# Schematic.net
KiCad netlist of a schematic drawn in EAGLE
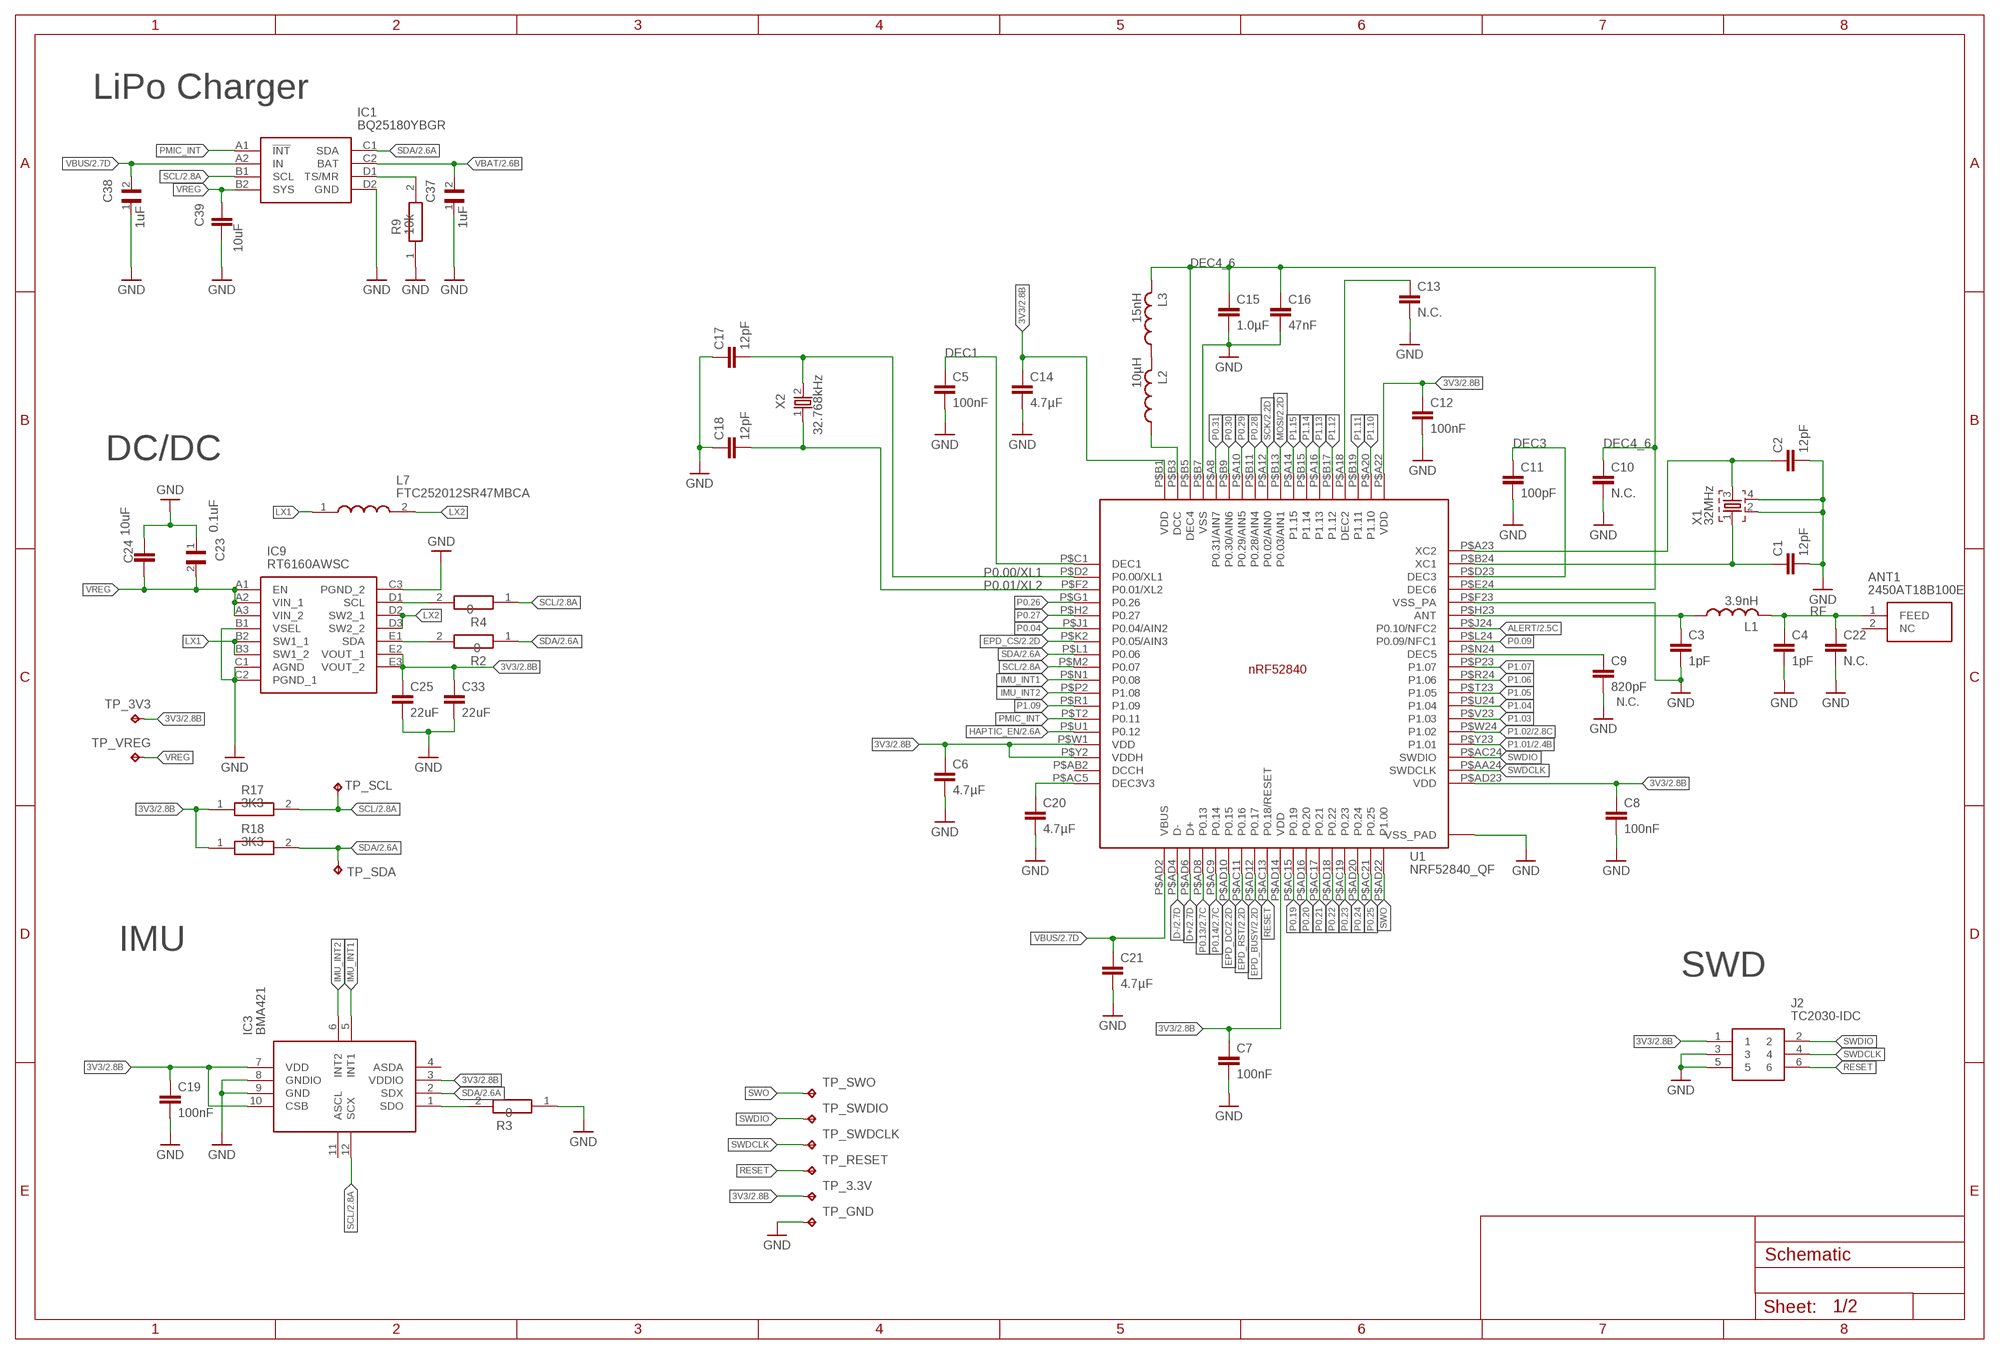
[diagram p0: schematic, sheet 1]
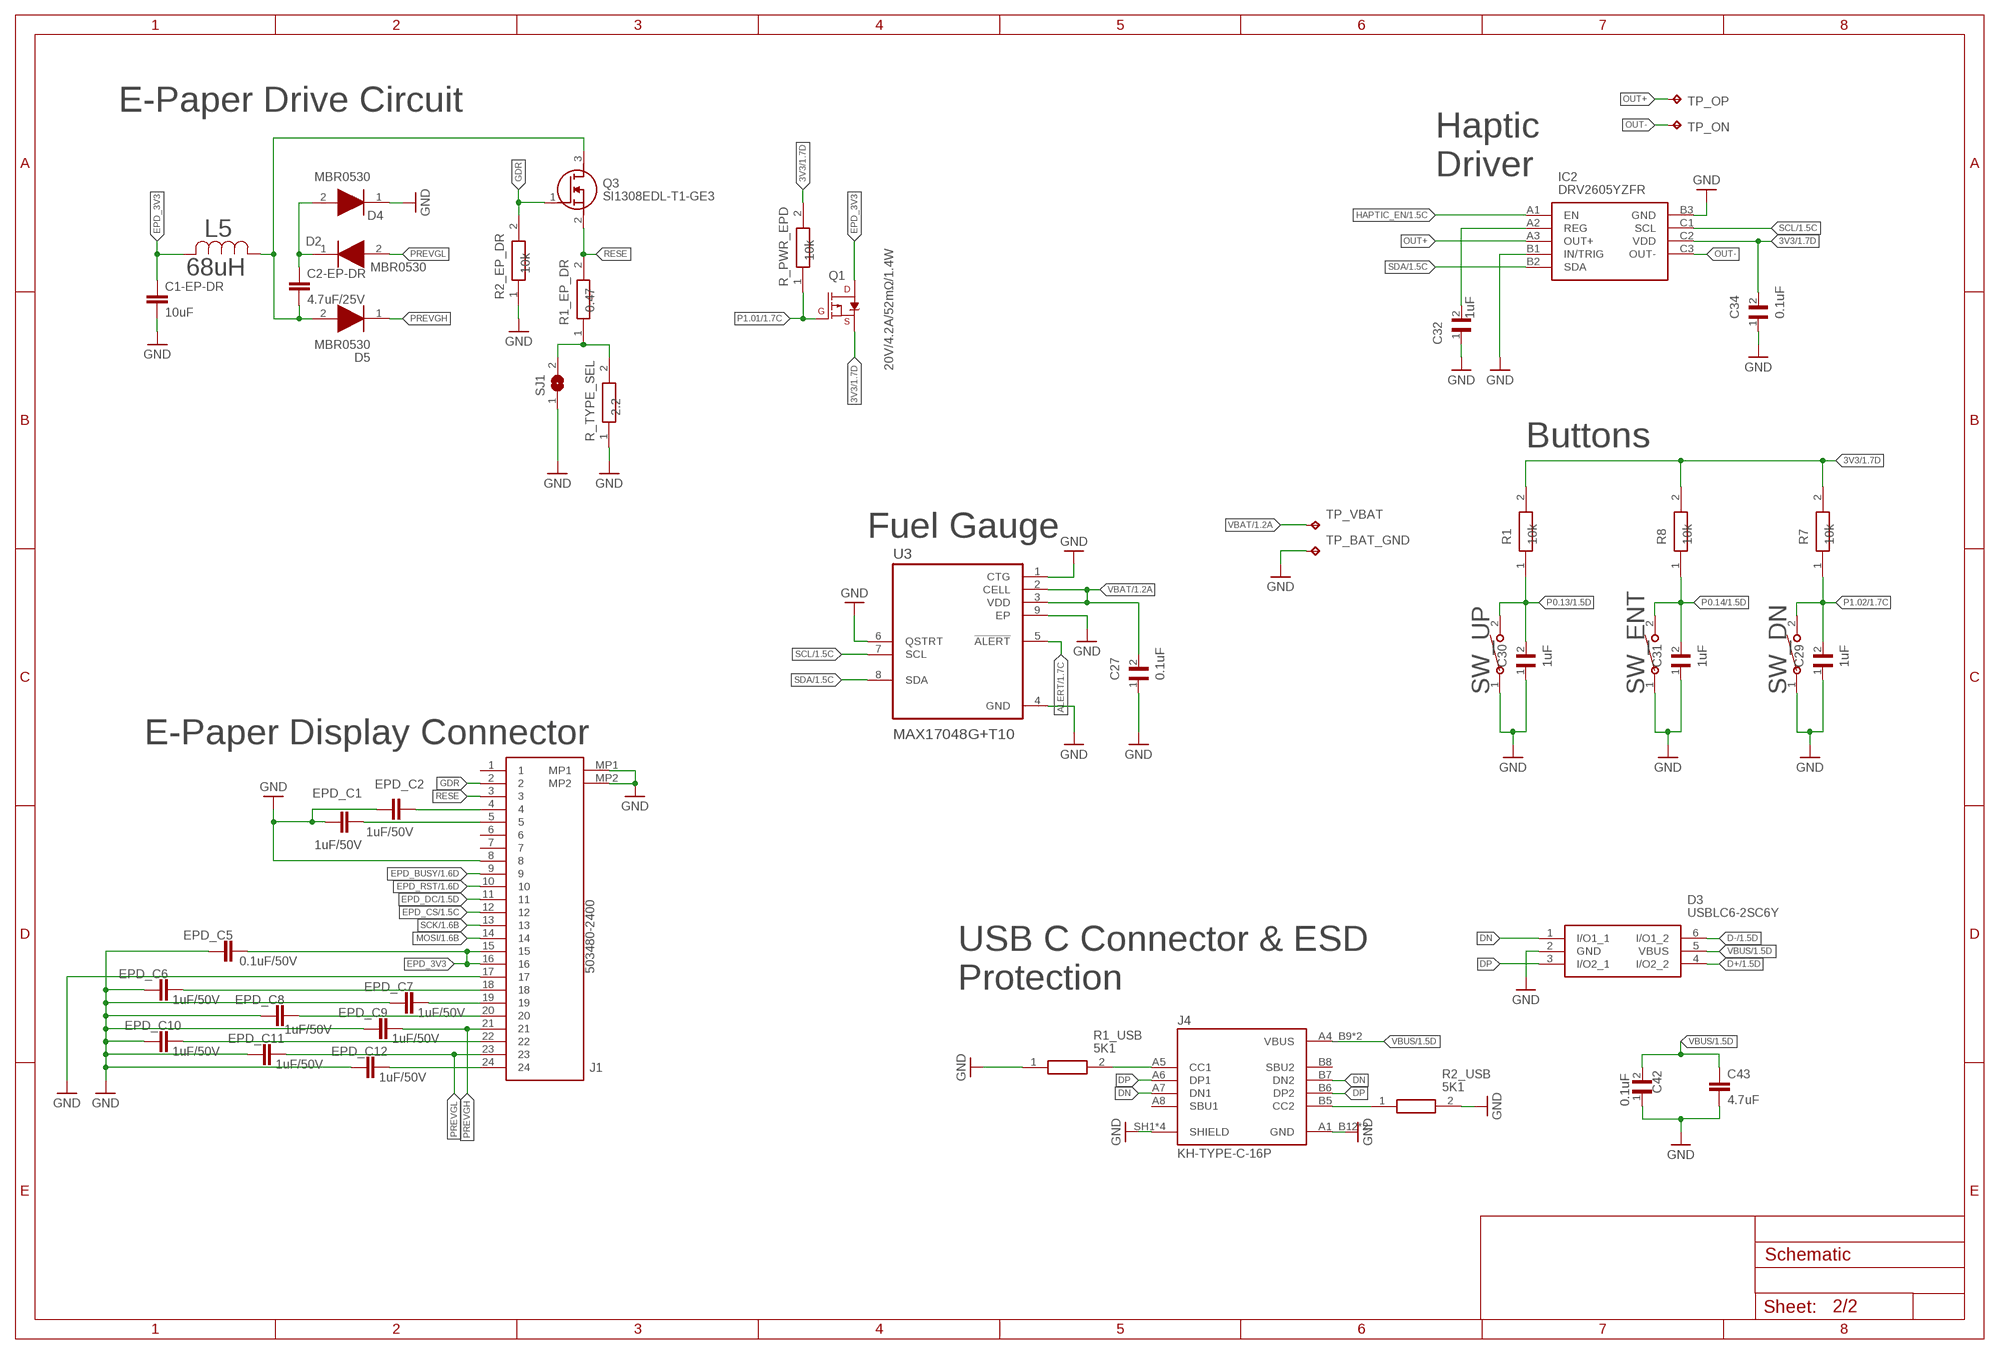
[diagram p1: schematic, sheet 2]

(export (version "E")
  (design (tool "Eeschema 10.0.6"))
  (components
    (comp (ref "ANT1")
      (value "2450AT18B100E")
      (footprint "eagle-import:2450AT18B100E_ANTC3216X140N")
      (fields (field (name "MOUSER_PART_NUMBER") "609-2450AT18B100E"))
      (libsource (lib "eagle-import") (part "2450AT18B100E_2450AT18B100E"))
    )
    (comp (ref "C1")
      (value "12pF")
      (footprint "eagle-import:NORDIC_NRF_3_RESC0201_L")
      (libsource (lib "eagle-import") (part "NORDIC_NRF_3_CAPACITOR_0201_L"))
    )
    (comp (ref "C2")
      (value "12pF")
      (footprint "eagle-import:NORDIC_NRF_3_RESC0201_L")
      (libsource (lib "eagle-import") (part "NORDIC_NRF_3_CAPACITOR_0201_L"))
    )
    (comp (ref "C3")
      (value "1pF")
      (footprint "eagle-import:NORDIC_NRF_3_RESC0201_L")
      (libsource (lib "eagle-import") (part "NORDIC_NRF_3_CAPACITOR_0201_L"))
    )
    (comp (ref "C4")
      (value "1pF")
      (footprint "eagle-import:NORDIC_NRF_3_RESC0201_L")
      (libsource (lib "eagle-import") (part "NORDIC_NRF_3_CAPACITOR_0201_L"))
    )
    (comp (ref "C5")
      (value "100nF")
      (footprint "eagle-import:NORDIC_NRF_3_RESC0201_L")
      (libsource (lib "eagle-import") (part "NORDIC_NRF_3_CAPACITOR_0201_L"))
    )
    (comp (ref "C6")
      (value "4.7µF")
      (footprint "eagle-import:NORDIC_NRF_3_RESC0201_L")
      (libsource (lib "eagle-import") (part "NORDIC_NRF_3_CAPACITOR_0201_L"))
    )
    (comp (ref "C7")
      (value "100nF")
      (footprint "eagle-import:NORDIC_NRF_3_RESC0201_L")
      (libsource (lib "eagle-import") (part "NORDIC_NRF_3_CAPACITOR_0201_L"))
    )
    (comp (ref "C8")
      (value "100nF")
      (footprint "eagle-import:NORDIC_NRF_3_RESC0201_L")
      (libsource (lib "eagle-import") (part "NORDIC_NRF_3_CAPACITOR_0201_L"))
    )
    (comp (ref "C9")
      (value "820pF")
      (footprint "eagle-import:NORDIC_NRF_3_RESC0201_L")
      (libsource (lib "eagle-import") (part "NORDIC_NRF_3_CAPACITOR_0201_L"))
    )
    (comp (ref "C10")
      (value "N.C.")
      (footprint "eagle-import:NORDIC_NRF_3_RESC0201_L")
      (libsource (lib "eagle-import") (part "NORDIC_NRF_3_CAPACITOR_0201_L"))
    )
    (comp (ref "C11")
      (value "100pF")
      (footprint "eagle-import:NORDIC_NRF_3_RESC0201_L")
      (libsource (lib "eagle-import") (part "NORDIC_NRF_3_CAPACITOR_0201_L"))
    )
    (comp (ref "C12")
      (value "100nF")
      (footprint "eagle-import:NORDIC_NRF_3_RESC0201_L")
      (libsource (lib "eagle-import") (part "NORDIC_NRF_3_CAPACITOR_0201_L"))
    )
    (comp (ref "C13")
      (value "N.C.")
      (footprint "eagle-import:NORDIC_NRF_3_RESC0201_L")
      (libsource (lib "eagle-import") (part "NORDIC_NRF_3_CAPACITOR_0201_L"))
    )
    (comp (ref "C14")
      (value "4.7µF")
      (footprint "eagle-import:NORDIC_NRF_3_RESC0201_L")
      (libsource (lib "eagle-import") (part "NORDIC_NRF_3_CAPACITOR_0201_L"))
    )
    (comp (ref "C15")
      (value "1.0µF")
      (footprint "eagle-import:NORDIC_NRF_3_RESC0201_L")
      (libsource (lib "eagle-import") (part "NORDIC_NRF_3_CAPACITOR_0201_L"))
    )
    (comp (ref "C16")
      (value "47nF")
      (footprint "eagle-import:NORDIC_NRF_3_RESC0201_L")
      (libsource (lib "eagle-import") (part "NORDIC_NRF_3_CAPACITOR_0201_L"))
    )
    (comp (ref "C17")
      (value "12pF")
      (footprint "eagle-import:NORDIC_NRF_3_RESC0201_L")
      (libsource (lib "eagle-import") (part "NORDIC_NRF_3_CAPACITOR_0201_L"))
    )
    (comp (ref "C18")
      (value "12pF")
      (footprint "eagle-import:NORDIC_NRF_3_RESC0201_L")
      (libsource (lib "eagle-import") (part "NORDIC_NRF_3_CAPACITOR_0201_L"))
    )
    (comp (ref "C19")
      (value "100nF")
      (footprint "eagle-import:NORDIC_NRF_3_RESC0201_L")
      (libsource (lib "eagle-import") (part "NORDIC_NRF_3_CAPACITOR_0201_L"))
    )
    (comp (ref "C20")
      (value "4.7µF")
      (footprint "eagle-import:NORDIC_NRF_3_RESC0201_L")
      (libsource (lib "eagle-import") (part "NORDIC_NRF_3_CAPACITOR_0201_L"))
    )
    (comp (ref "C21")
      (value "4.7µF")
      (footprint "eagle-import:NORDIC_NRF_3_RESC0201_L")
      (libsource (lib "eagle-import") (part "NORDIC_NRF_3_CAPACITOR_0201_L"))
    )
    (comp (ref "C22")
      (value "N.C.")
      (footprint "eagle-import:NORDIC_NRF_3_RESC0201_L")
      (libsource (lib "eagle-import") (part "NORDIC_NRF_3_CAPACITOR_0201_L"))
    )
    (comp (ref "C23")
      (value "0.1uF")
      (footprint "eagle-import:GRM011R60J152KE01L_2_CAPC0201X13N")
      (fields (field (name "MF") "Murata") (field (name "MP") "GRM011R60J152KE01L"))
      (libsource (lib "eagle-import") (part "GRM011R60J152KE01L_2_GRM011R60J152KE01L"))
    )
    (comp (ref "C24")
      (value "10uF")
      (footprint "eagle-import:NORDIC_NRF_3_RESC0201_L")
      (libsource (lib "eagle-import") (part "NORDIC_NRF_3_CAPACITOR_0201_L"))
    )
    (comp (ref "C25")
      (value "22uF")
      (footprint "eagle-import:NORDIC_NRF_3_RESC0201_L")
      (libsource (lib "eagle-import") (part "NORDIC_NRF_3_CAPACITOR_0201_L"))
    )
    (comp (ref "C33")
      (value "22uF")
      (footprint "eagle-import:NORDIC_NRF_3_RESC0201_L")
      (libsource (lib "eagle-import") (part "NORDIC_NRF_3_CAPACITOR_0201_L"))
    )
    (comp (ref "C37")
      (value "1uF")
      (footprint "eagle-import:GRM011R60J152KE01L_2_CAPC0201X13N")
      (fields (field (name "MF") "Murata") (field (name "MP") "GRM011R60J152KE01L"))
      (libsource (lib "eagle-import") (part "GRM011R60J152KE01L_2_GRM011R60J152KE01L"))
    )
    (comp (ref "C38")
      (value "1uF")
      (footprint "eagle-import:GRM011R60J152KE01L_2_CAPC0201X13N")
      (fields (field (name "MF") "Murata") (field (name "MP") "GRM011R60J152KE01L"))
      (libsource (lib "eagle-import") (part "GRM011R60J152KE01L_2_GRM011R60J152KE01L"))
    )
    (comp (ref "C39")
      (value "10uF")
      (footprint "eagle-import:NORDIC_NRF_3_RESC0201_L")
      (libsource (lib "eagle-import") (part "NORDIC_NRF_3_CAPACITOR_0201_L"))
    )
    (comp (ref "IC1")
      (value "BQ25180YBGR")
      (footprint "eagle-import:BQ25180YBGR_BGA8C40P2X4_100X155X50")
      (fields (field (name "MOUSER_PART_NUMBER") "595-BQ25180YBGR"))
      (libsource (lib "eagle-import") (part "BQ25180YBGR_BQ25180YBGR"))
    )
    (comp (ref "IC3")
      (value "BMA421")
      (footprint "eagle-import:BMA423_BMA423")
      (fields (field (name "ARROW_PART_NUMBER") "BMA423") (field (name "MOUSER_PART_NUMBER") "262-BMA423"))
      (libsource (lib "eagle-import") (part "BMA423_BMA423"))
    )
    (comp (ref "IC9")
      (value "RT6160AWSC")
      (footprint "eagle-import:RT6160AWSC_BGA15C40P3X5_140X230X60")
      (fields (field (name "MOUSER_PART_NUMBER") "835-RT6160AWSC"))
      (libsource (lib "eagle-import") (part "RT6160AWSC_RT6160AWSC"))
    )
    (comp (ref "J2")
      (value "TC2030-IDC")
      (footprint "eagle-import:TC2030-IDC_TC2030IDC")
      (libsource (lib "eagle-import") (part "TC2030-IDC_TC2030-IDC"))
    )
    (comp (ref "L1")
      (value "3.9nH")
      (footprint "eagle-import:NORDIC_NRF_2_RESC0402_L")
      (libsource (lib "eagle-import") (part "NORDIC_NRF_2_INDUCTOR_0402_L"))
    )
    (comp (ref "L2")
      (value "10µH")
      (footprint "eagle-import:NORDIC_NRF_2_RESC0402_L")
      (libsource (lib "eagle-import") (part "NORDIC_NRF_2_INDUCTOR_0402_L"))
    )
    (comp (ref "L3")
      (value "15nH")
      (footprint "eagle-import:NORDIC_NRF_2_RESC0402_L")
      (libsource (lib "eagle-import") (part "NORDIC_NRF_2_INDUCTOR_0402_L"))
    )
    (comp (ref "L7")
      (value "FTC252012SR47MBCA")
      (footprint "eagle-import:MLP2016SR47MT0S1_INDC2016X100N")
      (libsource (lib "eagle-import") (part "MLP2016SR47MT0S1_FTC252012SR47MBCA"))
    )
    (comp (ref "R2")
      (value "0")
      (footprint "eagle-import:CPF0201D7K68C1_0201")
      (libsource (lib "eagle-import") (part "CPF0201D7K68C1_CPF0201D7K68C1"))
    )
    (comp (ref "R3")
      (value "0")
      (footprint "eagle-import:CPF0201D7K68C1_0201")
      (libsource (lib "eagle-import") (part "CPF0201D7K68C1_CPF0201D7K68C1"))
    )
    (comp (ref "R4")
      (value "0")
      (footprint "eagle-import:CPF0201D7K68C1_0201")
      (libsource (lib "eagle-import") (part "CPF0201D7K68C1_CPF0201D7K68C1"))
    )
    (comp (ref "R9")
      (value "10k")
      (footprint "eagle-import:CPF0201D7K68C1_0201")
      (libsource (lib "eagle-import") (part "CPF0201D7K68C1_CPF0201D7K68C1"))
    )
    (comp (ref "R17")
      (value "3K3")
      (footprint "eagle-import:CPF0201D7K68C1_0201")
      (libsource (lib "eagle-import") (part "CPF0201D7K68C1_CPF0201D7K68C1"))
    )
    (comp (ref "R18")
      (value "3K3")
      (footprint "eagle-import:CPF0201D7K68C1_0201")
      (libsource (lib "eagle-import") (part "CPF0201D7K68C1_CPF0201D7K68C1"))
    )
    (comp (ref "TP_3.3V")
      (value "HECTOR_WATCH_1_TPTP20R")
      (footprint "eagle-import:HECTOR_WATCH_1_TP20R")
      (libsource (lib "eagle-import") (part "HECTOR_WATCH_1_TPTP20R"))
    )
    (comp (ref "TP_3V3")
      (value "HECTOR_WATCH_1_TPTP20R")
      (footprint "eagle-import:HECTOR_WATCH_1_TP20R")
      (libsource (lib "eagle-import") (part "HECTOR_WATCH_1_TPTP20R"))
    )
    (comp (ref "TP_GND")
      (value "HECTOR_WATCH_1_TPTP20R")
      (footprint "eagle-import:HECTOR_WATCH_1_TP20R")
      (libsource (lib "eagle-import") (part "HECTOR_WATCH_1_TPTP20R"))
    )
    (comp (ref "TP_RESET")
      (value "HECTOR_WATCH_1_TPTP20R")
      (footprint "eagle-import:HECTOR_WATCH_1_TP20R")
      (libsource (lib "eagle-import") (part "HECTOR_WATCH_1_TPTP20R"))
    )
    (comp (ref "TP_SCL")
      (value "HECTOR_WATCH_1_TPTP20R")
      (footprint "eagle-import:HECTOR_WATCH_1_TP20R")
      (libsource (lib "eagle-import") (part "HECTOR_WATCH_1_TPTP20R"))
    )
    (comp (ref "TP_SDA")
      (value "HECTOR_WATCH_1_TPTP20R")
      (footprint "eagle-import:HECTOR_WATCH_1_TP20R")
      (libsource (lib "eagle-import") (part "HECTOR_WATCH_1_TPTP20R"))
    )
    (comp (ref "TP_SWDCLK")
      (value "HECTOR_WATCH_1_TPTP20R")
      (footprint "eagle-import:HECTOR_WATCH_1_TP20R")
      (libsource (lib "eagle-import") (part "HECTOR_WATCH_1_TPTP20R"))
    )
    (comp (ref "TP_SWDIO")
      (value "HECTOR_WATCH_1_TPTP20R")
      (footprint "eagle-import:HECTOR_WATCH_1_TP20R")
      (libsource (lib "eagle-import") (part "HECTOR_WATCH_1_TPTP20R"))
    )
    (comp (ref "TP_SWO")
      (value "HECTOR_WATCH_1_TPTP20R")
      (footprint "eagle-import:HECTOR_WATCH_1_TP20R")
      (libsource (lib "eagle-import") (part "HECTOR_WATCH_1_TPTP20R"))
    )
    (comp (ref "TP_VREG")
      (value "HECTOR_WATCH_1_TPTP20R")
      (footprint "eagle-import:HECTOR_WATCH_1_TP20R")
      (libsource (lib "eagle-import") (part "HECTOR_WATCH_1_TPTP20R"))
    )
    (comp (ref "U1")
      (value "NRF52840_QF")
      (footprint "eagle-import:NORDIC_NRF_4_AQFN50P700X700X85_HS-74N")
      (libsource (lib "eagle-import") (part "NORDIC_NRF_4_NRF52840_QF"))
    )
    (comp (ref "X1")
      (value "32MHz")
      (footprint "eagle-import:NORDIC_NRF_BT-XTAL_2016_N")
      (libsource (lib "eagle-import") (part "NORDIC_NRF_XTAL_32MHZ"))
    )
    (comp (ref "X2")
      (value "32.768kHz")
      (footprint "eagle-import:NORDIC_NRF_1_XTAL_3215_N")
      (libsource (lib "eagle-import") (part "NORDIC_NRF_1_XTAL_32KHZ"))
    )
    (comp (ref "C1-EP-DR")
      (value "10uF")
      (footprint "eagle-import:NORDIC_NRF_3_RESC0201_L")
      (libsource (lib "eagle-import") (part "NORDIC_NRF_3_CAPACITOR_0201_L"))
    )
    (comp (ref "C2-EP-DR")
      (value "4.7uF/25V")
      (footprint "eagle-import:NORDIC_NRF_3_RESC0201_L")
      (libsource (lib "eagle-import") (part "NORDIC_NRF_3_CAPACITOR_0201_L"))
    )
    (comp (ref "C27")
      (value "0.1uF")
      (footprint "eagle-import:GRM011R60J152KE01L_2_CAPC0201X13N")
      (fields (field (name "MF") "Murata") (field (name "MP") "GRM011R60J152KE01L"))
      (libsource (lib "eagle-import") (part "GRM011R60J152KE01L_2_GRM011R60J152KE01L"))
    )
    (comp (ref "C29")
      (value "1uF")
      (footprint "eagle-import:GRM011R60J152KE01L_2_CAPC0201X13N")
      (fields (field (name "MF") "Murata") (field (name "MP") "GRM011R60J152KE01L"))
      (libsource (lib "eagle-import") (part "GRM011R60J152KE01L_2_GRM011R60J152KE01L"))
    )
    (comp (ref "C30")
      (value "1uF")
      (footprint "eagle-import:GRM011R60J152KE01L_2_CAPC0201X13N")
      (fields (field (name "MF") "Murata") (field (name "MP") "GRM011R60J152KE01L"))
      (libsource (lib "eagle-import") (part "GRM011R60J152KE01L_2_GRM011R60J152KE01L"))
    )
    (comp (ref "C31")
      (value "1uF")
      (footprint "eagle-import:GRM011R60J152KE01L_2_CAPC0201X13N")
      (fields (field (name "MF") "Murata") (field (name "MP") "GRM011R60J152KE01L"))
      (libsource (lib "eagle-import") (part "GRM011R60J152KE01L_2_GRM011R60J152KE01L"))
    )
    (comp (ref "C32")
      (value "1uF")
      (footprint "eagle-import:GRM011R60J152KE01L_2_CAPC0201X13N")
      (fields (field (name "MF") "Murata") (field (name "MP") "GRM011R60J152KE01L"))
      (libsource (lib "eagle-import") (part "GRM011R60J152KE01L_2_GRM011R60J152KE01L"))
    )
    (comp (ref "C34")
      (value "0.1uF")
      (footprint "eagle-import:GRM011R60J152KE01L_2_CAPC0201X13N")
      (fields (field (name "MF") "Murata") (field (name "MP") "GRM011R60J152KE01L"))
      (libsource (lib "eagle-import") (part "GRM011R60J152KE01L_2_GRM011R60J152KE01L"))
    )
    (comp (ref "C42")
      (value "0.1uF")
      (footprint "eagle-import:GRM011R60J152KE01L_2_CAPC0201X13N")
      (fields (field (name "MF") "Murata") (field (name "MP") "GRM011R60J152KE01L"))
      (libsource (lib "eagle-import") (part "GRM011R60J152KE01L_2_GRM011R60J152KE01L"))
    )
    (comp (ref "C43")
      (value "4.7uF")
      (footprint "eagle-import:NORDIC_NRF_3_RESC0201_L")
      (libsource (lib "eagle-import") (part "NORDIC_NRF_3_CAPACITOR_0201_L"))
    )
    (comp (ref "D2")
      (value "MBR0530")
      (footprint "eagle-import:ESP32_C6_LIBRARY_5_SOD3716X135N")
      (fields (field (name "MF") "ON Semiconductor"))
      (libsource (lib "eagle-import") (part "ESP32_C6_LIBRARY_5_MBR0530"))
    )
    (comp (ref "D3")
      (value "USBLC6-2SC6Y")
      (footprint "eagle-import:ESP32_C6_LIBRARY_3_SOT95P280X145-6N")
      (fields (field (name "MF") "STMicroelectronics"))
      (libsource (lib "eagle-import") (part "ESP32_C6_LIBRARY_3_USBLC6-2SC6Y"))
    )
    (comp (ref "D4")
      (value "MBR0530")
      (footprint "eagle-import:ESP32_C6_LIBRARY_5_SOD3716X135N")
      (fields (field (name "MF") "ON Semiconductor"))
      (libsource (lib "eagle-import") (part "ESP32_C6_LIBRARY_5_MBR0530"))
    )
    (comp (ref "D5")
      (value "MBR0530")
      (footprint "eagle-import:ESP32_C6_LIBRARY_5_SOD3716X135N")
      (fields (field (name "MF") "ON Semiconductor"))
      (libsource (lib "eagle-import") (part "ESP32_C6_LIBRARY_5_MBR0530"))
    )
    (comp (ref "EPD_C1")
      (value "1uF/50V")
      (footprint "eagle-import:NORDIC_NRF_3_RESC0201_L")
      (libsource (lib "eagle-import") (part "NORDIC_NRF_3_CAPACITOR_0201_L"))
    )
    (comp (ref "EPD_C2")
      (value "1uF/50V")
      (footprint "eagle-import:NORDIC_NRF_3_RESC0201_L")
      (libsource (lib "eagle-import") (part "NORDIC_NRF_3_CAPACITOR_0201_L"))
    )
    (comp (ref "EPD_C5")
      (value "0.1uF/50V")
      (footprint "eagle-import:NORDIC_NRF_3_RESC0201_L")
      (libsource (lib "eagle-import") (part "NORDIC_NRF_3_CAPACITOR_0201_L"))
    )
    (comp (ref "EPD_C6")
      (value "1uF/50V")
      (footprint "eagle-import:NORDIC_NRF_3_RESC0201_L")
      (libsource (lib "eagle-import") (part "NORDIC_NRF_3_CAPACITOR_0201_L"))
    )
    (comp (ref "EPD_C7")
      (value "1uF/50V")
      (footprint "eagle-import:NORDIC_NRF_3_RESC0201_L")
      (libsource (lib "eagle-import") (part "NORDIC_NRF_3_CAPACITOR_0201_L"))
    )
    (comp (ref "EPD_C8")
      (value "1uF/50V")
      (footprint "eagle-import:NORDIC_NRF_3_RESC0201_L")
      (libsource (lib "eagle-import") (part "NORDIC_NRF_3_CAPACITOR_0201_L"))
    )
    (comp (ref "EPD_C9")
      (value "1uF/50V")
      (footprint "eagle-import:NORDIC_NRF_3_RESC0201_L")
      (libsource (lib "eagle-import") (part "NORDIC_NRF_3_CAPACITOR_0201_L"))
    )
    (comp (ref "EPD_C10")
      (value "1uF/50V")
      (footprint "eagle-import:NORDIC_NRF_3_RESC0201_L")
      (libsource (lib "eagle-import") (part "NORDIC_NRF_3_CAPACITOR_0201_L"))
    )
    (comp (ref "EPD_C11")
      (value "1uF/50V")
      (footprint "eagle-import:NORDIC_NRF_3_RESC0201_L")
      (libsource (lib "eagle-import") (part "NORDIC_NRF_3_CAPACITOR_0201_L"))
    )
    (comp (ref "EPD_C12")
      (value "1uF/50V")
      (footprint "eagle-import:NORDIC_NRF_3_RESC0201_L")
      (libsource (lib "eagle-import") (part "NORDIC_NRF_3_CAPACITOR_0201_L"))
    )
    (comp (ref "IC2")
      (value "DRV2605YZFR")
      (footprint "eagle-import:DRV2605YZFR_BGA9C50P3X3_144X144X62")
      (libsource (lib "eagle-import") (part "DRV2605YZFR_DRV2605YZFR"))
    )
    (comp (ref "J1")
      (value "503480-2400")
      (footprint "eagle-import:503480-2400_5034802400")
      (fields (field (name "MOUSER_PART_NUMBER") "538-503480-2400"))
      (libsource (lib "eagle-import") (part "503480-2400_503480-2400"))
    )
    (comp (ref "J4")
      (value "KH-TYPE-C-16P")
      (footprint "eagle-import:KH-TYPE-C-16P_KINGHELM_KH-TYPE-C-16P")
      (fields (field (name "MF") "kinghelm"))
      (libsource (lib "eagle-import") (part "KH-TYPE-C-16P_KH-TYPE-C-16P"))
    )
    (comp (ref "L5")
      (value "68uH")
      (footprint "eagle-import:ESP32_C6_LIBRARY_2_IND_4828-WE-TPC_WRE")
      (fields
        (field (name "MANUFACTURER_PART_NUMBER") "744043680")
        (field (name "COPYRIGHT") "Copyright (C) 2024 Ultra Librarian. All rights reserved.")
      )
      (libsource (lib "eagle-import") (part "ESP32_C6_LIBRARY_2_744043680IND_4828-WE-TPC_WRE"))
    )
    (comp (ref "Q1")
      (value "20V/4.2A/52mΩ/1.4W")
      (footprint "eagle-import:ESP32_C6_LIBRARY_4_ESP32_C6_LIBRARY_4_ESP32_C6_LIBRARY_4_ESP32_C6_LIBRARY_4_ESP32_WROVER_SPARKFUN-DISCRETESEMI_SOT23-3")
      (libsource (lib "eagle-import") (part "ESP32_C6_LIBRARY_4_ESP32_WROVER_SPARKFUN-DISCRETESEMI_MOSFET_PCH-DMG2305UX-7"))
    )
    (comp (ref "Q3")
      (value "SI1308EDL-T1-GE3")
      (footprint "eagle-import:ESP32_C6_LIBRARY_6_SOT65P210X110-3N")
      (fields (field (name "MF") "Vishay Siliconix"))
      (libsource (lib "eagle-import") (part "ESP32_C6_LIBRARY_6_SI1308EDL-T1-GE3"))
    )
    (comp (ref "R1")
      (value "10k")
      (footprint "eagle-import:CPF0201D7K68C1_0201")
      (libsource (lib "eagle-import") (part "CPF0201D7K68C1_CPF0201D7K68C1"))
    )
    (comp (ref "R1_EP_DR")
      (value "0.47")
      (footprint "eagle-import:ERA-1AEB3401C_0201")
      (libsource (lib "eagle-import") (part "ERA-1AEB3401C_CPF0201D7K68C1"))
    )
    (comp (ref "R1_USB")
      (value "5K1")
      (footprint "eagle-import:CPF0201D7K68C1_0201")
      (libsource (lib "eagle-import") (part "CPF0201D7K68C1_CPF0201D7K68C1"))
    )
    (comp (ref "R2_EP_DR")
      (value "10k")
      (footprint "eagle-import:ERA-1AEB3401C_0201")
      (libsource (lib "eagle-import") (part "ERA-1AEB3401C_CPF0201D7K68C1"))
    )
    (comp (ref "R2_USB")
      (value "5K1")
      (footprint "eagle-import:ERA-1AEB3401C_0201")
      (libsource (lib "eagle-import") (part "ERA-1AEB3401C_CPF0201D7K68C1"))
    )
    (comp (ref "R7")
      (value "10k")
      (footprint "eagle-import:CPF0201D7K68C1_0201")
      (libsource (lib "eagle-import") (part "CPF0201D7K68C1_CPF0201D7K68C1"))
    )
    (comp (ref "R8")
      (value "10k")
      (footprint "eagle-import:CPF0201D7K68C1_0201")
      (libsource (lib "eagle-import") (part "CPF0201D7K68C1_CPF0201D7K68C1"))
    )
    (comp (ref "R_PWR_EPD")
      (value "10k")
      (footprint "eagle-import:CPF0201D7K68C1_0201")
      (libsource (lib "eagle-import") (part "CPF0201D7K68C1_CPF0201D7K68C1"))
    )
    (comp (ref "R_TYPE_SEL")
      (value "2.2")
      (footprint "eagle-import:ERA-1AEB3401C_0201")
      (libsource (lib "eagle-import") (part "ERA-1AEB3401C_CPF0201D7K68C1"))
    )
    (comp (ref "SJ1")
      (value "ESP32_C6_LIBRARY_7_JUMPER_SJ")
      (footprint "eagle-import:ESP32_C6_LIBRARY_7_JUMPER_SJ")
      (libsource (lib "eagle-import") (part "ESP32_C6_LIBRARY_7_JUMPER_SJ"))
    )
    (comp (ref "SW_DN")
      (value "2025-10-22_07-23-44_LIBRARY_EVP-AKE31ASW_EVP-AKE31A_PAN")
      (footprint "eagle-import:2025-10-22_07-23-44_LIBRARY_SW_EVP-AKE31A_PAN")
      (fields
        (field (name "MANUFACTURER_PART_NUMBER") "EVP-AKE31A")
        (field (name "COPYRIGHT") "Copyright (C) 2025 Ultra Librarian. All rights reserved.")
      )
      (libsource (lib "eagle-import") (part "2025-10-22_07-23-44_LIBRARY_EVP-AKE31ASW_EVP-AKE31A_PAN"))
    )
    (comp (ref "SW_ENT")
      (value "2025-10-22_07-23-44_LIBRARY_EVP-AKE31ASW_EVP-AKE31A_PAN")
      (footprint "eagle-import:2025-10-22_07-23-44_LIBRARY_SW_EVP-AKE31A_PAN")
      (fields
        (field (name "MANUFACTURER_PART_NUMBER") "EVP-AKE31A")
        (field (name "COPYRIGHT") "Copyright (C) 2025 Ultra Librarian. All rights reserved.")
      )
      (libsource (lib "eagle-import") (part "2025-10-22_07-23-44_LIBRARY_EVP-AKE31ASW_EVP-AKE31A_PAN"))
    )
    (comp (ref "SW_UP")
      (value "2025-10-22_07-23-44_LIBRARY_EVP-AKE31ASW_EVP-AKE31A_PAN")
      (footprint "eagle-import:2025-10-22_07-23-44_LIBRARY_SW_EVP-AKE31A_PAN")
      (fields
        (field (name "MANUFACTURER_PART_NUMBER") "EVP-AKE31A")
        (field (name "COPYRIGHT") "Copyright (C) 2025 Ultra Librarian. All rights reserved.")
      )
      (libsource (lib "eagle-import") (part "2025-10-22_07-23-44_LIBRARY_EVP-AKE31ASW_EVP-AKE31A_PAN"))
    )
    (comp (ref "TP_BAT_GND")
      (value "HECTOR_WATCH_1_TPTP20R")
      (footprint "eagle-import:HECTOR_WATCH_1_TP20R")
      (libsource (lib "eagle-import") (part "HECTOR_WATCH_1_TPTP20R"))
    )
    (comp (ref "TP_ON")
      (value "HECTOR_WATCH_1_TPTP20R")
      (footprint "eagle-import:HECTOR_WATCH_1_TP20R")
      (libsource (lib "eagle-import") (part "HECTOR_WATCH_1_TPTP20R"))
    )
    (comp (ref "TP_OP")
      (value "HECTOR_WATCH_1_TPTP20R")
      (footprint "eagle-import:HECTOR_WATCH_1_TP20R")
      (libsource (lib "eagle-import") (part "HECTOR_WATCH_1_TPTP20R"))
    )
    (comp (ref "TP_VBAT")
      (value "HECTOR_WATCH_1_TPTP20R")
      (footprint "eagle-import:HECTOR_WATCH_1_TP20R")
      (libsource (lib "eagle-import") (part "HECTOR_WATCH_1_TPTP20R"))
    )
    (comp (ref "U3")
      (value "MAX17048G+T10")
      (footprint "eagle-import:ESP32_C6_LIBRARY_SON50P200X200X80-9N")
      (fields (field (name "MF") "Analog Devices"))
      (libsource (lib "eagle-import") (part "ESP32_C6_LIBRARY_MAX17048G+T10"))
    )
  )
  (nets
    (net (code "1") (name "3V3") (class "Default")
      (node (ref "C12") (pin "1") (pinfunction "1_1") (pintype "passive"))
      (node (ref "C14") (pin "1") (pinfunction "1_1") (pintype "passive"))
      (node (ref "C19") (pin "1") (pinfunction "1_1") (pintype "passive"))
      (node (ref "C25") (pin "1") (pinfunction "1_1") (pintype "passive"))
      (node (ref "C33") (pin "1") (pinfunction "1_1") (pintype "passive"))
      (node (ref "C34") (pin "2") (pinfunction "2_2") (pintype "passive"))
      (node (ref "C6") (pin "1") (pinfunction "1_1") (pintype "passive"))
      (node (ref "C7") (pin "1") (pinfunction "1_1") (pintype "passive"))
      (node (ref "C8") (pin "1") (pinfunction "1_1") (pintype "passive"))
      (node (ref "IC2") (pin "C2") (pinfunction "VDD_C2") (pintype "bidirectional"))
      (node (ref "IC3") (pin "10") (pinfunction "CSB_10") (pintype "bidirectional"))
      (node (ref "IC3") (pin "3") (pinfunction "VDDIO_3") (pintype "bidirectional"))
      (node (ref "IC3") (pin "7") (pinfunction "VDD_7") (pintype "bidirectional"))
      (node (ref "IC9") (pin "E2") (pinfunction "VOUT_1_E2") (pintype "bidirectional"))
      (node (ref "IC9") (pin "E3") (pinfunction "VOUT_2_E3") (pintype "bidirectional"))
      (node (ref "J2") (pin "1") (pinfunction "1_1") (pintype "bidirectional"))
      (node (ref "Q1") (pin "2") (pinfunction "S_2") (pintype "bidirectional"))
      (node (ref "R1") (pin "2") (pinfunction "2_2") (pintype "bidirectional"))
      (node (ref "R17") (pin "1") (pinfunction "1_1") (pintype "bidirectional"))
      (node (ref "R18") (pin "1") (pinfunction "1_1") (pintype "bidirectional"))
      (node (ref "R7") (pin "2") (pinfunction "2_2") (pintype "bidirectional"))
      (node (ref "R8") (pin "2") (pinfunction "2_2") (pintype "bidirectional"))
      (node (ref "R_PWR_EPD") (pin "2") (pinfunction "2_2") (pintype "bidirectional"))
      (node (ref "TP_3.3V") (pin "TP") (pinfunction "TP_TP") (pintype "input"))
      (node (ref "TP_3V3") (pin "TP") (pinfunction "TP_TP") (pintype "input"))
      (node (ref "U1") (pin "P$A22") (pinfunction "VDD_P$A22") (pintype "power_in"))
      (node (ref "U1") (pin "P$AD14") (pinfunction "VDD_P$AD14") (pintype "power_in"))
      (node (ref "U1") (pin "P$AD23") (pinfunction "VDD_P$AD23") (pintype "power_in"))
      (node (ref "U1") (pin "P$B1") (pinfunction "VDD_P$B1") (pintype "power_in"))
      (node (ref "U1") (pin "P$W1") (pinfunction "VDD_P$W1") (pintype "power_in"))
      (node (ref "U1") (pin "P$Y2") (pinfunction "VDDH_P$Y2") (pintype "power_in"))
    )
    (net (code "2") (name "ALERT") (class "Default")
      (node (ref "U1") (pin "P$J24") (pinfunction "P0.10/NFC2_P$J24") (pintype "bidirectional"))
      (node (ref "U3") (pin "5") (pinfunction "~{ALERT}_5") (pintype "output"))
    )
    (net (code "3") (name "D+") (class "Default")
      (node (ref "D3") (pin "4") (pinfunction "I/O2_2_4") (pintype "bidirectional"))
      (node (ref "U1") (pin "P$AD6") (pinfunction "D+_P$AD6") (pintype "bidirectional"))
    )
    (net (code "4") (name "D-") (class "Default")
      (node (ref "D3") (pin "6") (pinfunction "I/O1_2_6") (pintype "bidirectional"))
      (node (ref "U1") (pin "P$AD4") (pinfunction "D-_P$AD4") (pintype "bidirectional"))
    )
    (net (code "5") (name "DEC1") (class "Default")
      (node (ref "C5") (pin "1") (pinfunction "1_1") (pintype "passive"))
      (node (ref "U1") (pin "P$C1") (pinfunction "DEC1_P$C1") (pintype "power_in"))
    )
    (net (code "6") (name "DEC3") (class "Default")
      (node (ref "C11") (pin "1") (pinfunction "1_1") (pintype "passive"))
      (node (ref "U1") (pin "P$D23") (pinfunction "DEC3_P$D23") (pintype "bidirectional"))
    )
    (net (code "7") (name "DEC4_6") (class "Default")
      (node (ref "C10") (pin "1") (pinfunction "1_1") (pintype "passive"))
      (node (ref "C15") (pin "1") (pinfunction "1_1") (pintype "passive"))
      (node (ref "C16") (pin "1") (pinfunction "1_1") (pintype "passive"))
      (node (ref "L3") (pin "2") (pinfunction "2_2") (pintype "passive"))
      (node (ref "U1") (pin "P$B5") (pinfunction "DEC4_P$B5") (pintype "power_in"))
      (node (ref "U1") (pin "P$E24") (pinfunction "DEC6_P$E24") (pintype "bidirectional"))
    )
    (net (code "8") (name "DN") (class "Default")
      (node (ref "D3") (pin "1") (pinfunction "I/O1_1_1") (pintype "bidirectional"))
      (node (ref "J4") (pin "A7") (pinfunction "DN1_A7") (pintype "bidirectional"))
      (node (ref "J4") (pin "B7") (pinfunction "DN2_B7") (pintype "bidirectional"))
    )
    (net (code "9") (name "DP") (class "Default")
      (node (ref "D3") (pin "3") (pinfunction "I/O2_1_3") (pintype "bidirectional"))
      (node (ref "J4") (pin "A6") (pinfunction "DP1_A6") (pintype "bidirectional"))
      (node (ref "J4") (pin "B6") (pinfunction "DP2_B6") (pintype "bidirectional"))
    )
    (net (code "10") (name "EPD_3V3") (class "Default")
      (node (ref "C1-EP-DR") (pin "1") (pinfunction "1_1") (pintype "passive"))
      (node (ref "EPD_C5") (pin "2") (pinfunction "2_2") (pintype "passive"))
      (node (ref "J1") (pin "15") (pinfunction "15_15") (pintype "bidirectional"))
      (node (ref "J1") (pin "16") (pinfunction "16_16") (pintype "bidirectional"))
      (node (ref "L5") (pin "2") (pinfunction "2_2") (pintype "passive"))
      (node (ref "Q1") (pin "3") (pinfunction "D_3") (pintype "bidirectional"))
    )
    (net (code "11") (name "EPD_BUSY") (class "Default")
      (node (ref "J1") (pin "9") (pinfunction "9_9") (pintype "bidirectional"))
      (node (ref "U1") (pin "P$AD12") (pinfunction "P0.17_P$AD12") (pintype "bidirectional"))
    )
    (net (code "12") (name "EPD_CS") (class "Default")
      (node (ref "J1") (pin "12") (pinfunction "12_12") (pintype "bidirectional"))
      (node (ref "U1") (pin "P$K2") (pinfunction "P0.05/AIN3_P$K2") (pintype "bidirectional"))
    )
    (net (code "13") (name "EPD_DC") (class "Default")
      (node (ref "J1") (pin "11") (pinfunction "11_11") (pintype "bidirectional"))
      (node (ref "U1") (pin "P$AD10") (pinfunction "P0.15_P$AD10") (pintype "bidirectional"))
    )
    (net (code "14") (name "EPD_RST") (class "Default")
      (node (ref "J1") (pin "10") (pinfunction "10_10") (pintype "bidirectional"))
      (node (ref "U1") (pin "P$AC11") (pinfunction "P0.16_P$AC11") (pintype "bidirectional"))
    )
    (net (code "15") (name "GDR") (class "Default")
      (node (ref "J1") (pin "2") (pinfunction "2_2") (pintype "bidirectional"))
      (node (ref "Q3") (pin "1") (pinfunction "G_1") (pintype "bidirectional"))
      (node (ref "R2_EP_DR") (pin "2") (pinfunction "2_2") (pintype "bidirectional"))
    )
    (net (code "16") (name "GND") (class "Default")
      (node (ref "C1") (pin "2") (pinfunction "2_2") (pintype "passive"))
      (node (ref "C1-EP-DR") (pin "2") (pinfunction "2_2") (pintype "passive"))
      (node (ref "C10") (pin "2") (pinfunction "2_2") (pintype "passive"))
      (node (ref "C11") (pin "2") (pinfunction "2_2") (pintype "passive"))
      (node (ref "C12") (pin "2") (pinfunction "2_2") (pintype "passive"))
      (node (ref "C13") (pin "2") (pinfunction "2_2") (pintype "passive"))
      (node (ref "C14") (pin "2") (pinfunction "2_2") (pintype "passive"))
      (node (ref "C15") (pin "2") (pinfunction "2_2") (pintype "passive"))
      (node (ref "C16") (pin "2") (pinfunction "2_2") (pintype "passive"))
      (node (ref "C17") (pin "1") (pinfunction "1_1") (pintype "passive"))
      (node (ref "C18") (pin "1") (pinfunction "1_1") (pintype "passive"))
      (node (ref "C19") (pin "2") (pinfunction "2_2") (pintype "passive"))
      (node (ref "C2") (pin "2") (pinfunction "2_2") (pintype "passive"))
      (node (ref "C20") (pin "2") (pinfunction "2_2") (pintype "passive"))
      (node (ref "C21") (pin "2") (pinfunction "2_2") (pintype "passive"))
      (node (ref "C22") (pin "2") (pinfunction "2_2") (pintype "passive"))
      (node (ref "C23") (pin "1") (pinfunction "1_1") (pintype "passive"))
      (node (ref "C24") (pin "2") (pinfunction "2_2") (pintype "passive"))
      (node (ref "C25") (pin "2") (pinfunction "2_2") (pintype "passive"))
      (node (ref "C27") (pin "1") (pinfunction "1_1") (pintype "passive"))
      (node (ref "C29") (pin "1") (pinfunction "1_1") (pintype "passive"))
      (node (ref "C3") (pin "2") (pinfunction "2_2") (pintype "passive"))
      (node (ref "C30") (pin "1") (pinfunction "1_1") (pintype "passive"))
      (node (ref "C31") (pin "1") (pinfunction "1_1") (pintype "passive"))
      (node (ref "C32") (pin "1") (pinfunction "1_1") (pintype "passive"))
      (node (ref "C33") (pin "2") (pinfunction "2_2") (pintype "passive"))
      (node (ref "C34") (pin "1") (pinfunction "1_1") (pintype "passive"))
      (node (ref "C37") (pin "1") (pinfunction "1_1") (pintype "passive"))
      (node (ref "C38") (pin "1") (pinfunction "1_1") (pintype "passive"))
      (node (ref "C39") (pin "2") (pinfunction "2_2") (pintype "passive"))
      (node (ref "C4") (pin "2") (pinfunction "2_2") (pintype "passive"))
      (node (ref "C42") (pin "1") (pinfunction "1_1") (pintype "passive"))
      (node (ref "C43") (pin "2") (pinfunction "2_2") (pintype "passive"))
      (node (ref "C5") (pin "2") (pinfunction "2_2") (pintype "passive"))
      (node (ref "C6") (pin "2") (pinfunction "2_2") (pintype "passive"))
      (node (ref "C7") (pin "2") (pinfunction "2_2") (pintype "passive"))
      (node (ref "C8") (pin "2") (pinfunction "2_2") (pintype "passive"))
      (node (ref "C9") (pin "2") (pinfunction "2_2") (pintype "passive"))
      (node (ref "D3") (pin "2") (pinfunction "GND_2") (pintype "bidirectional"))
      (node (ref "D4") (pin "1") (pinfunction "K_1") (pintype "bidirectional"))
      (node (ref "EPD_C1") (pin "1") (pinfunction "1_1") (pintype "passive"))
      (node (ref "EPD_C10") (pin "1") (pinfunction "1_1") (pintype "passive"))
      (node (ref "EPD_C11") (pin "1") (pinfunction "1_1") (pintype "passive"))
      (node (ref "EPD_C12") (pin "1") (pinfunction "1_1") (pintype "passive"))
      (node (ref "EPD_C2") (pin "1") (pinfunction "1_1") (pintype "passive"))
      (node (ref "EPD_C5") (pin "1") (pinfunction "1_1") (pintype "passive"))
      (node (ref "EPD_C6") (pin "1") (pinfunction "1_1") (pintype "passive"))
      (node (ref "EPD_C7") (pin "1") (pinfunction "1_1") (pintype "passive"))
      (node (ref "EPD_C8") (pin "1") (pinfunction "1_1") (pintype "passive"))
      (node (ref "EPD_C9") (pin "1") (pinfunction "1_1") (pintype "passive"))
      (node (ref "IC1") (pin "D2") (pinfunction "GND_D2") (pintype "bidirectional"))
      (node (ref "IC2") (pin "B1") (pinfunction "IN/TRIG_B1") (pintype "bidirectional"))
      (node (ref "IC2") (pin "B3") (pinfunction "GND_B3") (pintype "bidirectional"))
      (node (ref "IC3") (pin "8") (pinfunction "GNDIO_8") (pintype "bidirectional"))
      (node (ref "IC3") (pin "9") (pinfunction "GND_9") (pintype "bidirectional"))
      (node (ref "IC9") (pin "B1") (pinfunction "VSEL_B1") (pintype "bidirectional"))
      (node (ref "IC9") (pin "C1") (pinfunction "AGND_C1") (pintype "bidirectional"))
      (node (ref "IC9") (pin "C2") (pinfunction "PGND_1_C2") (pintype "bidirectional"))
      (node (ref "IC9") (pin "C3") (pinfunction "PGND_2_C3") (pintype "bidirectional"))
      (node (ref "J1") (pin "17") (pinfunction "17_17") (pintype "bidirectional"))
      (node (ref "J1") (pin "8") (pinfunction "8_8") (pintype "bidirectional"))
      (node (ref "J1") (pin "MP1") (pinfunction "MP1_MP1") (pintype "bidirectional"))
      (node (ref "J1") (pin "MP2") (pinfunction "MP2_MP2") (pintype "bidirectional"))
      (node (ref "J2") (pin "3") (pinfunction "3_3") (pintype "bidirectional"))
      (node (ref "J2") (pin "5") (pinfunction "5_5") (pintype "bidirectional"))
      (node (ref "J4") (pin "A12_B1") (pinfunction "GND_A12_B1") (pintype "power_in"))
      (node (ref "J4") (pin "A1_B12") (pinfunction "GND_A1_B12") (pintype "power_in"))
      (node (ref "J4") (pin "SH1") (pinfunction "SHIELD_SH1") (pintype "passive"))
      (node (ref "J4") (pin "SH2") (pinfunction "SHIELD_SH2") (pintype "passive"))
      (node (ref "J4") (pin "SH3") (pinfunction "SHIELD_SH3") (pintype "passive"))
      (node (ref "J4") (pin "SH4") (pinfunction "SHIELD_SH4") (pintype "passive"))
      (node (ref "R1_USB") (pin "1") (pinfunction "1_1") (pintype "bidirectional"))
      (node (ref "R2_EP_DR") (pin "1") (pinfunction "1_1") (pintype "bidirectional"))
      (node (ref "R2_USB") (pin "2") (pinfunction "2_2") (pintype "bidirectional"))
      (node (ref "R3") (pin "1") (pinfunction "1_1") (pintype "bidirectional"))
      (node (ref "R9") (pin "1") (pinfunction "1_1") (pintype "bidirectional"))
      (node (ref "R_TYPE_SEL") (pin "1") (pinfunction "1_1") (pintype "bidirectional"))
      (node (ref "SJ1") (pin "1") (pinfunction "1_1") (pintype "passive"))
      (node (ref "SW_DN") (pin "1") (pinfunction "1_1") (pintype "passive"))
      (node (ref "SW_ENT") (pin "1") (pinfunction "1_1") (pintype "passive"))
      (node (ref "SW_UP") (pin "1") (pinfunction "1_1") (pintype "passive"))
      (node (ref "TP_BAT_GND") (pin "TP") (pinfunction "TP_TP") (pintype "input"))
      (node (ref "TP_GND") (pin "TP") (pinfunction "TP_TP") (pintype "input"))
      (node (ref "U1") (pin "P$74") (pinfunction "VSS_PAD_P$74") (pintype "bidirectional"))
      (node (ref "U1") (pin "P$75") (pinfunction "VSS_PAD_P$75") (pintype "bidirectional"))
      (node (ref "U1") (pin "P$76") (pinfunction "VSS_PAD_P$76") (pintype "bidirectional"))
      (node (ref "U1") (pin "P$77") (pinfunction "VSS_PAD_P$77") (pintype "bidirectional"))
      (node (ref "U1") (pin "P$78") (pinfunction "VSS_PAD_P$78") (pintype "bidirectional"))
      (node (ref "U1") (pin "P$79") (pinfunction "VSS_PAD_P$79") (pintype "bidirectional"))
      (node (ref "U1") (pin "P$80") (pinfunction "VSS_PAD_P$80") (pintype "bidirectional"))
      (node (ref "U1") (pin "P$81") (pinfunction "VSS_PAD_P$81") (pintype "bidirectional"))
      (node (ref "U1") (pin "P$82") (pinfunction "VSS_PAD_P$82") (pintype "bidirectional"))
      (node (ref "U1") (pin "P$83") (pinfunction "VSS_PAD_P$83") (pintype "bidirectional"))
      (node (ref "U1") (pin "P$84") (pinfunction "VSS_PAD_P$84") (pintype "bidirectional"))
      (node (ref "U1") (pin "P$85") (pinfunction "VSS_PAD_P$85") (pintype "bidirectional"))
      (node (ref "U1") (pin "P$86") (pinfunction "VSS_PAD_P$86") (pintype "bidirectional"))
      (node (ref "U1") (pin "P$87") (pinfunction "VSS_PAD_P$87") (pintype "bidirectional"))
      (node (ref "U1") (pin "P$88") (pinfunction "VSS_PAD_P$88") (pintype "bidirectional"))
      (node (ref "U1") (pin "P$89") (pinfunction "VSS_PAD_P$89") (pintype "bidirectional"))
      (node (ref "U1") (pin "P$90") (pinfunction "VSS_PAD_P$90") (pintype "bidirectional"))
      (node (ref "U1") (pin "P$B7") (pinfunction "VSS_P$B7") (pintype "power_in"))
      (node (ref "U1") (pin "P$F23") (pinfunction "VSS_PA_P$F23") (pintype "bidirectional"))
      (node (ref "U3") (pin "1") (pinfunction "CTG_1") (pintype "power_in"))
      (node (ref "U3") (pin "4") (pinfunction "GND_4") (pintype "power_in"))
      (node (ref "U3") (pin "6") (pinfunction "QSTRT_6") (pintype "input"))
      (node (ref "U3") (pin "9") (pinfunction "EP_9") (pintype "power_in"))
      (node (ref "X1") (pin "2") (pinfunction "2_2") (pintype "passive"))
      (node (ref "X1") (pin "4") (pinfunction "4_4") (pintype "passive"))
    )
    (net (code "17") (name "HAPTIC_EN") (class "Default")
      (node (ref "IC2") (pin "A1") (pinfunction "EN_A1") (pintype "bidirectional"))
      (node (ref "U1") (pin "P$U1") (pinfunction "P0.12_P$U1") (pintype "bidirectional"))
    )
    (net (code "18") (name "IMU_INT1") (class "Default")
      (node (ref "IC3") (pin "5") (pinfunction "INT1_5") (pintype "bidirectional"))
      (node (ref "U1") (pin "P$N1") (pinfunction "P0.08_P$N1") (pintype "bidirectional"))
    )
    (net (code "19") (name "IMU_INT2") (class "Default")
      (node (ref "IC3") (pin "6") (pinfunction "INT2_6") (pintype "bidirectional"))
      (node (ref "U1") (pin "P$P2") (pinfunction "P1.08_P$P2") (pintype "bidirectional"))
    )
    (net (code "20") (name "LX1") (class "Default")
      (node (ref "IC9") (pin "B2") (pinfunction "SW1_1_B2") (pintype "bidirectional"))
      (node (ref "IC9") (pin "B3") (pinfunction "SW1_2_B3") (pintype "bidirectional"))
      (node (ref "L7") (pin "1") (pinfunction "1_1") (pintype "bidirectional"))
    )
    (net (code "21") (name "LX2") (class "Default")
      (node (ref "IC9") (pin "D2") (pinfunction "SW2_1_D2") (pintype "bidirectional"))
      (node (ref "IC9") (pin "D3") (pinfunction "SW2_2_D3") (pintype "bidirectional"))
      (node (ref "L7") (pin "2") (pinfunction "2_2") (pintype "bidirectional"))
    )
    (net (code "22") (name "MOSI") (class "Default")
      (node (ref "J1") (pin "14") (pinfunction "14_14") (pintype "bidirectional"))
      (node (ref "U1") (pin "P$B13") (pinfunction "P0.03/AIN1_P$B13") (pintype "bidirectional"))
    )
    (net (code "23") (name "Net-(D2-K)") (class "Default")
      (node (ref "C2-EP-DR") (pin "1") (pinfunction "1_1") (pintype "passive"))
      (node (ref "D2") (pin "1") (pinfunction "K_1") (pintype "bidirectional"))
      (node (ref "D4") (pin "2") (pinfunction "A_2") (pintype "bidirectional"))
    )
    (net (code "24") (name "Net-(D5-A)") (class "Default")
      (node (ref "C2-EP-DR") (pin "2") (pinfunction "2_2") (pintype "passive"))
      (node (ref "D5") (pin "2") (pinfunction "A_2") (pintype "bidirectional"))
      (node (ref "L5") (pin "1") (pinfunction "1_1") (pintype "passive"))
      (node (ref "Q3") (pin "3") (pinfunction "D_3") (pintype "bidirectional"))
    )
    (net (code "25") (name "Net-(EPD_C1-Pad2)") (class "Default")
      (node (ref "EPD_C1") (pin "2") (pinfunction "2_2") (pintype "passive"))
      (node (ref "J1") (pin "5") (pinfunction "5_5") (pintype "bidirectional"))
    )
    (net (code "26") (name "Net-(EPD_C2-Pad2)") (class "Default")
      (node (ref "EPD_C2") (pin "2") (pinfunction "2_2") (pintype "passive"))
      (node (ref "J1") (pin "4") (pinfunction "4_4") (pintype "bidirectional"))
    )
    (net (code "27") (name "Net-(EPD_C6-Pad2)") (class "Default")
      (node (ref "EPD_C6") (pin "2") (pinfunction "2_2") (pintype "passive"))
      (node (ref "J1") (pin "18") (pinfunction "18_18") (pintype "bidirectional"))
    )
    (net (code "28") (name "Net-(EPD_C7-Pad2)") (class "Default")
      (node (ref "EPD_C7") (pin "2") (pinfunction "2_2") (pintype "passive"))
      (node (ref "J1") (pin "19") (pinfunction "19_19") (pintype "bidirectional"))
    )
    (net (code "29") (name "Net-(EPD_C8-Pad2)") (class "Default")
      (node (ref "EPD_C8") (pin "2") (pinfunction "2_2") (pintype "passive"))
      (node (ref "J1") (pin "20") (pinfunction "20_20") (pintype "bidirectional"))
    )
    (net (code "30") (name "Net-(EPD_C10-Pad2)") (class "Default")
      (node (ref "EPD_C10") (pin "2") (pinfunction "2_2") (pintype "passive"))
      (node (ref "J1") (pin "22") (pinfunction "22_22") (pintype "bidirectional"))
    )
    (net (code "31") (name "Net-(EPD_C12-Pad2)") (class "Default")
      (node (ref "EPD_C12") (pin "2") (pinfunction "2_2") (pintype "passive"))
      (node (ref "J1") (pin "24") (pinfunction "24_24") (pintype "bidirectional"))
    )
    (net (code "32") (name "Net-(IC1-TS{slash}MR)") (class "Default")
      (node (ref "IC1") (pin "D1") (pinfunction "TS/MR_D1") (pintype "bidirectional"))
      (node (ref "R9") (pin "2") (pinfunction "2_2") (pintype "bidirectional"))
    )
    (net (code "33") (name "Net-(IC2-REG)") (class "Default")
      (node (ref "C32") (pin "2") (pinfunction "2_2") (pintype "passive"))
      (node (ref "IC2") (pin "A2") (pinfunction "REG_A2") (pintype "bidirectional"))
    )
    (net (code "34") (name "Net-(IC3-SDO)") (class "Default")
      (node (ref "IC3") (pin "1") (pinfunction "SDO_1") (pintype "bidirectional"))
      (node (ref "R3") (pin "2") (pinfunction "2_2") (pintype "bidirectional"))
    )
    (net (code "35") (name "Net-(IC9-SCL)") (class "Default")
      (node (ref "IC9") (pin "D1") (pinfunction "SCL_D1") (pintype "bidirectional"))
      (node (ref "R4") (pin "2") (pinfunction "2_2") (pintype "bidirectional"))
    )
    (net (code "36") (name "Net-(IC9-SDA)") (class "Default")
      (node (ref "IC9") (pin "E1") (pinfunction "SDA_E1") (pintype "bidirectional"))
      (node (ref "R2") (pin "2") (pinfunction "2_2") (pintype "bidirectional"))
    )
    (net (code "37") (name "Net-(J4-CC1)") (class "Default")
      (node (ref "J4") (pin "A5") (pinfunction "CC1_A5") (pintype "bidirectional"))
      (node (ref "R1_USB") (pin "2") (pinfunction "2_2") (pintype "bidirectional"))
    )
    (net (code "38") (name "Net-(J4-CC2)") (class "Default")
      (node (ref "J4") (pin "B5") (pinfunction "CC2_B5") (pintype "bidirectional"))
      (node (ref "R2_USB") (pin "1") (pinfunction "1_1") (pintype "bidirectional"))
    )
    (net (code "39") (name "Net-(L2-Pad2)") (class "Default")
      (node (ref "L2") (pin "2") (pinfunction "2_2") (pintype "passive"))
      (node (ref "L3") (pin "1") (pinfunction "1_1") (pintype "passive"))
    )
    (net (code "40") (name "Net-(R1_EP_DR-Pad1)") (class "Default")
      (node (ref "R1_EP_DR") (pin "1") (pinfunction "1_1") (pintype "bidirectional"))
      (node (ref "R_TYPE_SEL") (pin "2") (pinfunction "2_2") (pintype "bidirectional"))
      (node (ref "SJ1") (pin "2") (pinfunction "2_2") (pintype "passive"))
    )
    (net (code "41") (name "Net-(U1-ANT)") (class "Default")
      (node (ref "C3") (pin "1") (pinfunction "1_1") (pintype "passive"))
      (node (ref "L1") (pin "1") (pinfunction "1_1") (pintype "passive"))
      (node (ref "U1") (pin "P$H23") (pinfunction "ANT_P$H23") (pintype "bidirectional"))
    )
    (net (code "42") (name "Net-(U1-DCC)") (class "Default")
      (node (ref "L2") (pin "1") (pinfunction "1_1") (pintype "passive"))
      (node (ref "U1") (pin "P$B3") (pinfunction "DCC_P$B3") (pintype "output"))
    )
    (net (code "43") (name "Net-(U1-DEC2)") (class "Default")
      (node (ref "C13") (pin "1") (pinfunction "1_1") (pintype "passive"))
      (node (ref "U1") (pin "P$A18") (pinfunction "DEC2_P$A18") (pintype "bidirectional"))
    )
    (net (code "44") (name "Net-(U1-DEC3V3)") (class "Default")
      (node (ref "C20") (pin "1") (pinfunction "1_1") (pintype "passive"))
      (node (ref "U1") (pin "P$AC5") (pinfunction "DEC3V3_P$AC5") (pintype "bidirectional"))
    )
    (net (code "45") (name "Net-(U1-DEC5)") (class "Default")
      (node (ref "C9") (pin "1") (pinfunction "1_1") (pintype "passive"))
      (node (ref "U1") (pin "P$N24") (pinfunction "DEC5_P$N24") (pintype "bidirectional"))
    )
    (net (code "46") (name "Net-(U1-XC1)") (class "Default")
      (node (ref "C1") (pin "1") (pinfunction "1_1") (pintype "passive"))
      (node (ref "U1") (pin "P$B24") (pinfunction "XC1_P$B24") (pintype "input"))
      (node (ref "X1") (pin "1") (pinfunction "1_1") (pintype "passive"))
    )
    (net (code "47") (name "Net-(U1-XC2)") (class "Default")
      (node (ref "C2") (pin "1") (pinfunction "1_1") (pintype "passive"))
      (node (ref "U1") (pin "P$A23") (pinfunction "XC2_P$A23") (pintype "output"))
      (node (ref "X1") (pin "3") (pinfunction "3_3") (pintype "passive"))
    )
    (net (code "48") (name "OUT+") (class "Default")
      (node (ref "IC2") (pin "A3") (pinfunction "OUT+_A3") (pintype "bidirectional"))
      (node (ref "TP_OP") (pin "TP") (pinfunction "TP_TP") (pintype "input"))
    )
    (net (code "49") (name "OUT-") (class "Default")
      (node (ref "IC2") (pin "C3") (pinfunction "OUT-_C3") (pintype "bidirectional"))
      (node (ref "TP_ON") (pin "TP") (pinfunction "TP_TP") (pintype "input"))
    )
    (net (code "50") (name "P0.00{slash}XL1") (class "Default")
      (node (ref "C17") (pin "2") (pinfunction "2_2") (pintype "passive"))
      (node (ref "U1") (pin "P$D2") (pinfunction "P0.00/XL1_P$D2") (pintype "bidirectional"))
      (node (ref "X2") (pin "2") (pinfunction "2_2") (pintype "passive"))
    )
    (net (code "51") (name "P0.01{slash}XL2") (class "Default")
      (node (ref "C18") (pin "2") (pinfunction "2_2") (pintype "passive"))
      (node (ref "U1") (pin "P$F2") (pinfunction "P0.01/XL2_P$F2") (pintype "bidirectional"))
      (node (ref "X2") (pin "1") (pinfunction "1_1") (pintype "passive"))
    )
    (net (code "52") (name "P0.04") (class "Default")
      (node (ref "U1") (pin "P$J1") (pinfunction "P0.04/AIN2_P$J1") (pintype "bidirectional"))
    )
    (net (code "53") (name "P0.09") (class "Default")
      (node (ref "U1") (pin "P$L24") (pinfunction "P0.09/NFC1_P$L24") (pintype "bidirectional"))
    )
    (net (code "54") (name "P0.13") (class "Default")
      (node (ref "C30") (pin "2") (pinfunction "2_2") (pintype "passive"))
      (node (ref "R1") (pin "1") (pinfunction "1_1") (pintype "bidirectional"))
      (node (ref "SW_UP") (pin "2") (pinfunction "2_2") (pintype "passive"))
      (node (ref "U1") (pin "P$AD8") (pinfunction "P0.13_P$AD8") (pintype "bidirectional"))
    )
    (net (code "55") (name "P0.14") (class "Default")
      (node (ref "C31") (pin "2") (pinfunction "2_2") (pintype "passive"))
      (node (ref "R8") (pin "1") (pinfunction "1_1") (pintype "bidirectional"))
      (node (ref "SW_ENT") (pin "2") (pinfunction "2_2") (pintype "passive"))
      (node (ref "U1") (pin "P$AC9") (pinfunction "P0.14_P$AC9") (pintype "bidirectional"))
    )
    (net (code "56") (name "P0.19") (class "Default")
      (node (ref "U1") (pin "P$AC15") (pinfunction "P0.19_P$AC15") (pintype "bidirectional"))
    )
    (net (code "57") (name "P0.20") (class "Default")
      (node (ref "U1") (pin "P$AD16") (pinfunction "P0.20_P$AD16") (pintype "bidirectional"))
    )
    (net (code "58") (name "P0.21") (class "Default")
      (node (ref "U1") (pin "P$AC17") (pinfunction "P0.21_P$AC17") (pintype "bidirectional"))
    )
    (net (code "59") (name "P0.22") (class "Default")
      (node (ref "U1") (pin "P$AD18") (pinfunction "P0.22_P$AD18") (pintype "bidirectional"))
    )
    (net (code "60") (name "P0.23") (class "Default")
      (node (ref "U1") (pin "P$AC19") (pinfunction "P0.23_P$AC19") (pintype "bidirectional"))
    )
    (net (code "61") (name "P0.24") (class "Default")
      (node (ref "U1") (pin "P$AD20") (pinfunction "P0.24_P$AD20") (pintype "bidirectional"))
    )
    (net (code "62") (name "P0.25") (class "Default")
      (node (ref "U1") (pin "P$AC21") (pinfunction "P0.25_P$AC21") (pintype "bidirectional"))
    )
    (net (code "63") (name "P0.26") (class "Default")
      (node (ref "U1") (pin "P$G1") (pinfunction "P0.26_P$G1") (pintype "bidirectional"))
    )
    (net (code "64") (name "P0.27") (class "Default")
      (node (ref "U1") (pin "P$H2") (pinfunction "P0.27_P$H2") (pintype "bidirectional"))
    )
    (net (code "65") (name "P0.28") (class "Default")
      (node (ref "U1") (pin "P$B11") (pinfunction "P0.28/AIN4_P$B11") (pintype "bidirectional"))
    )
    (net (code "66") (name "P0.29") (class "Default")
      (node (ref "U1") (pin "P$A10") (pinfunction "P0.29/AIN5_P$A10") (pintype "bidirectional"))
    )
    (net (code "67") (name "P0.30") (class "Default")
      (node (ref "U1") (pin "P$B9") (pinfunction "P0.30/AIN6_P$B9") (pintype "bidirectional"))
    )
    (net (code "68") (name "P0.31") (class "Default")
      (node (ref "U1") (pin "P$A8") (pinfunction "P0.31/AIN7_P$A8") (pintype "bidirectional"))
    )
    (net (code "69") (name "P1.01") (class "Default")
      (node (ref "Q1") (pin "1") (pinfunction "G_1") (pintype "bidirectional"))
      (node (ref "R_PWR_EPD") (pin "1") (pinfunction "1_1") (pintype "bidirectional"))
      (node (ref "U1") (pin "P$Y23") (pinfunction "P1.01_P$Y23") (pintype "bidirectional"))
    )
    (net (code "70") (name "P1.02") (class "Default")
      (node (ref "C29") (pin "2") (pinfunction "2_2") (pintype "passive"))
      (node (ref "R7") (pin "1") (pinfunction "1_1") (pintype "bidirectional"))
      (node (ref "SW_DN") (pin "2") (pinfunction "2_2") (pintype "passive"))
      (node (ref "U1") (pin "P$W24") (pinfunction "P1.02_P$W24") (pintype "bidirectional"))
    )
    (net (code "71") (name "P1.03") (class "Default")
      (node (ref "U1") (pin "P$V23") (pinfunction "P1.03_P$V23") (pintype "bidirectional"))
    )
    (net (code "72") (name "P1.04") (class "Default")
      (node (ref "U1") (pin "P$U24") (pinfunction "P1.04_P$U24") (pintype "bidirectional"))
    )
    (net (code "73") (name "P1.05") (class "Default")
      (node (ref "U1") (pin "P$T23") (pinfunction "P1.05_P$T23") (pintype "bidirectional"))
    )
    (net (code "74") (name "P1.06") (class "Default")
      (node (ref "U1") (pin "P$R24") (pinfunction "P1.06_P$R24") (pintype "bidirectional"))
    )
    (net (code "75") (name "P1.07") (class "Default")
      (node (ref "U1") (pin "P$P23") (pinfunction "P1.07_P$P23") (pintype "bidirectional"))
    )
    (net (code "76") (name "P1.09") (class "Default")
      (node (ref "U1") (pin "P$R1") (pinfunction "P1.09_P$R1") (pintype "bidirectional"))
    )
    (net (code "77") (name "P1.10") (class "Default")
      (node (ref "U1") (pin "P$A20") (pinfunction "P1.10_P$A20") (pintype "bidirectional"))
    )
    (net (code "78") (name "P1.11") (class "Default")
      (node (ref "U1") (pin "P$B19") (pinfunction "P1.11_P$B19") (pintype "bidirectional"))
    )
    (net (code "79") (name "P1.12") (class "Default")
      (node (ref "U1") (pin "P$B17") (pinfunction "P1.12_P$B17") (pintype "bidirectional"))
    )
    (net (code "80") (name "P1.13") (class "Default")
      (node (ref "U1") (pin "P$A16") (pinfunction "P1.13_P$A16") (pintype "bidirectional"))
    )
    (net (code "81") (name "P1.14") (class "Default")
      (node (ref "U1") (pin "P$B15") (pinfunction "P1.14_P$B15") (pintype "bidirectional"))
    )
    (net (code "82") (name "P1.15") (class "Default")
      (node (ref "U1") (pin "P$A14") (pinfunction "P1.15_P$A14") (pintype "bidirectional"))
    )
    (net (code "83") (name "PMIC_INT") (class "Default")
      (node (ref "IC1") (pin "A1") (pinfunction "~{INT}_A1") (pintype "bidirectional"))
      (node (ref "U1") (pin "P$T2") (pinfunction "P0.11_P$T2") (pintype "bidirectional"))
    )
    (net (code "84") (name "PREVGH") (class "Default")
      (node (ref "D5") (pin "1") (pinfunction "K_1") (pintype "bidirectional"))
      (node (ref "EPD_C9") (pin "2") (pinfunction "2_2") (pintype "passive"))
      (node (ref "J1") (pin "21") (pinfunction "21_21") (pintype "bidirectional"))
    )
    (net (code "85") (name "PREVGL") (class "Default")
      (node (ref "D2") (pin "2") (pinfunction "A_2") (pintype "bidirectional"))
      (node (ref "EPD_C11") (pin "2") (pinfunction "2_2") (pintype "passive"))
      (node (ref "J1") (pin "23") (pinfunction "23_23") (pintype "bidirectional"))
    )
    (net (code "86") (name "RESE") (class "Default")
      (node (ref "J1") (pin "3") (pinfunction "3_3") (pintype "bidirectional"))
      (node (ref "Q3") (pin "2") (pinfunction "S_2") (pintype "bidirectional"))
      (node (ref "R1_EP_DR") (pin "2") (pinfunction "2_2") (pintype "bidirectional"))
    )
    (net (code "87") (name "RESET") (class "Default")
      (node (ref "J2") (pin "6") (pinfunction "6_6") (pintype "bidirectional"))
      (node (ref "TP_RESET") (pin "TP") (pinfunction "TP_TP") (pintype "input"))
      (node (ref "U1") (pin "P$AC13") (pinfunction "P0.18/RESET_P$AC13") (pintype "bidirectional"))
    )
    (net (code "88") (name "RF") (class "Default")
      (node (ref "ANT1") (pin "1") (pinfunction "FEED_1") (pintype "input"))
      (node (ref "C22") (pin "1") (pinfunction "1_1") (pintype "passive"))
      (node (ref "C4") (pin "1") (pinfunction "1_1") (pintype "passive"))
      (node (ref "L1") (pin "2") (pinfunction "2_2") (pintype "passive"))
    )
    (net (code "89") (name "SCK") (class "Default")
      (node (ref "J1") (pin "13") (pinfunction "13_13") (pintype "bidirectional"))
      (node (ref "U1") (pin "P$A12") (pinfunction "P0.02/AIN0_P$A12") (pintype "bidirectional"))
    )
    (net (code "90") (name "SCL") (class "Default")
      (node (ref "IC1") (pin "B1") (pinfunction "SCL_B1") (pintype "bidirectional"))
      (node (ref "IC2") (pin "C1") (pinfunction "SCL_C1") (pintype "bidirectional"))
      (node (ref "IC3") (pin "12") (pinfunction "SCX_12") (pintype "bidirectional"))
      (node (ref "R17") (pin "2") (pinfunction "2_2") (pintype "bidirectional"))
      (node (ref "R4") (pin "1") (pinfunction "1_1") (pintype "bidirectional"))
      (node (ref "TP_SCL") (pin "TP") (pinfunction "TP_TP") (pintype "input"))
      (node (ref "U1") (pin "P$M2") (pinfunction "P0.07_P$M2") (pintype "bidirectional"))
      (node (ref "U3") (pin "7") (pinfunction "SCL_7") (pintype "input"))
    )
    (net (code "91") (name "SDA") (class "Default")
      (node (ref "IC1") (pin "C1") (pinfunction "SDA_C1") (pintype "bidirectional"))
      (node (ref "IC2") (pin "B2") (pinfunction "SDA_B2") (pintype "bidirectional"))
      (node (ref "IC3") (pin "2") (pinfunction "SDX_2") (pintype "bidirectional"))
      (node (ref "R18") (pin "2") (pinfunction "2_2") (pintype "bidirectional"))
      (node (ref "R2") (pin "1") (pinfunction "1_1") (pintype "bidirectional"))
      (node (ref "TP_SDA") (pin "TP") (pinfunction "TP_TP") (pintype "input"))
      (node (ref "U1") (pin "P$L1") (pinfunction "P0.06_P$L1") (pintype "bidirectional"))
      (node (ref "U3") (pin "8") (pinfunction "SDA_8") (pintype "bidirectional"))
    )
    (net (code "92") (name "SWDCLK") (class "Default")
      (node (ref "J2") (pin "4") (pinfunction "4_4") (pintype "bidirectional"))
      (node (ref "TP_SWDCLK") (pin "TP") (pinfunction "TP_TP") (pintype "input"))
      (node (ref "U1") (pin "P$AA24") (pinfunction "SWDCLK_P$AA24") (pintype "input"))
    )
    (net (code "93") (name "SWDIO") (class "Default")
      (node (ref "J2") (pin "2") (pinfunction "2_2") (pintype "bidirectional"))
      (node (ref "TP_SWDIO") (pin "TP") (pinfunction "TP_TP") (pintype "input"))
      (node (ref "U1") (pin "P$AC24") (pinfunction "SWDIO_P$AC24") (pintype "bidirectional"))
    )
    (net (code "94") (name "SWO") (class "Default")
      (node (ref "TP_SWO") (pin "TP") (pinfunction "TP_TP") (pintype "input"))
      (node (ref "U1") (pin "P$AD22") (pinfunction "P1.00_P$AD22") (pintype "bidirectional"))
    )
    (net (code "95") (name "VBAT") (class "Default")
      (node (ref "C27") (pin "2") (pinfunction "2_2") (pintype "passive"))
      (node (ref "C37") (pin "2") (pinfunction "2_2") (pintype "passive"))
      (node (ref "IC1") (pin "C2") (pinfunction "BAT_C2") (pintype "bidirectional"))
      (node (ref "TP_VBAT") (pin "TP") (pinfunction "TP_TP") (pintype "input"))
      (node (ref "U3") (pin "2") (pinfunction "CELL_2") (pintype "power_in"))
      (node (ref "U3") (pin "3") (pinfunction "VDD_3") (pintype "power_in"))
    )
    (net (code "96") (name "VBUS") (class "Default")
      (node (ref "C21") (pin "1") (pinfunction "1_1") (pintype "passive"))
      (node (ref "C38") (pin "2") (pinfunction "2_2") (pintype "passive"))
      (node (ref "C42") (pin "2") (pinfunction "2_2") (pintype "passive"))
      (node (ref "C43") (pin "1") (pinfunction "1_1") (pintype "passive"))
      (node (ref "D3") (pin "5") (pinfunction "VBUS_5") (pintype "bidirectional"))
      (node (ref "IC1") (pin "A2") (pinfunction "IN_A2") (pintype "bidirectional"))
      (node (ref "J4") (pin "A4_B9") (pinfunction "VBUS_A4_B9") (pintype "power_in"))
      (node (ref "J4") (pin "A9_B4") (pinfunction "VBUS_A9_B4") (pintype "power_in"))
      (node (ref "U1") (pin "P$AD2") (pinfunction "VBUS_P$AD2") (pintype "power_in"))
    )
    (net (code "97") (name "VREG") (class "Default")
      (node (ref "C23") (pin "2") (pinfunction "2_2") (pintype "passive"))
      (node (ref "C24") (pin "1") (pinfunction "1_1") (pintype "passive"))
      (node (ref "C39") (pin "1") (pinfunction "1_1") (pintype "passive"))
      (node (ref "IC1") (pin "B2") (pinfunction "SYS_B2") (pintype "bidirectional"))
      (node (ref "IC9") (pin "A1") (pinfunction "EN_A1") (pintype "bidirectional"))
      (node (ref "IC9") (pin "A2") (pinfunction "VIN_1_A2") (pintype "bidirectional"))
      (node (ref "IC9") (pin "A3") (pinfunction "VIN_2_A3") (pintype "bidirectional"))
      (node (ref "TP_VREG") (pin "TP") (pinfunction "TP_TP") (pintype "input"))
    )
    (net (code "98") (name "unconnected-(ANT1-NC-Pad2)") (class "Default")
      (node (ref "ANT1") (pin "2") (pinfunction "NC_2") (pintype "no_connect"))
    )
    (net (code "99") (name "unconnected-(IC3-ASCL-Pad11)") (class "Default")
      (node (ref "IC3") (pin "11") (pinfunction "ASCL_11") (pintype "bidirectional"))
    )
    (net (code "100") (name "unconnected-(IC3-ASDA-Pad4)") (class "Default")
      (node (ref "IC3") (pin "4") (pinfunction "ASDA_4") (pintype "bidirectional"))
    )
    (net (code "101") (name "unconnected-(J1-Pad1)") (class "Default")
      (node (ref "J1") (pin "1") (pinfunction "1_1") (pintype "bidirectional"))
    )
    (net (code "102") (name "unconnected-(J1-Pad6)") (class "Default")
      (node (ref "J1") (pin "6") (pinfunction "6_6") (pintype "bidirectional"))
    )
    (net (code "103") (name "unconnected-(J1-Pad7)") (class "Default")
      (node (ref "J1") (pin "7") (pinfunction "7_7") (pintype "bidirectional"))
    )
    (net (code "104") (name "unconnected-(J4-SBU1-PadA8)") (class "Default")
      (node (ref "J4") (pin "A8") (pinfunction "SBU1_A8") (pintype "bidirectional"))
    )
    (net (code "105") (name "unconnected-(J4-SBU2-PadB8)") (class "Default")
      (node (ref "J4") (pin "B8") (pinfunction "SBU2_B8") (pintype "bidirectional"))
    )
    (net (code "106") (name "unconnected-(U1-DCCH-PadP$AB2)") (class "Default")
      (node (ref "U1") (pin "P$AB2") (pinfunction "DCCH_P$AB2") (pintype "bidirectional"))
    )
  )
)
